# esp_heart.net
KiCad netlist of a schematic drawn in EAGLE
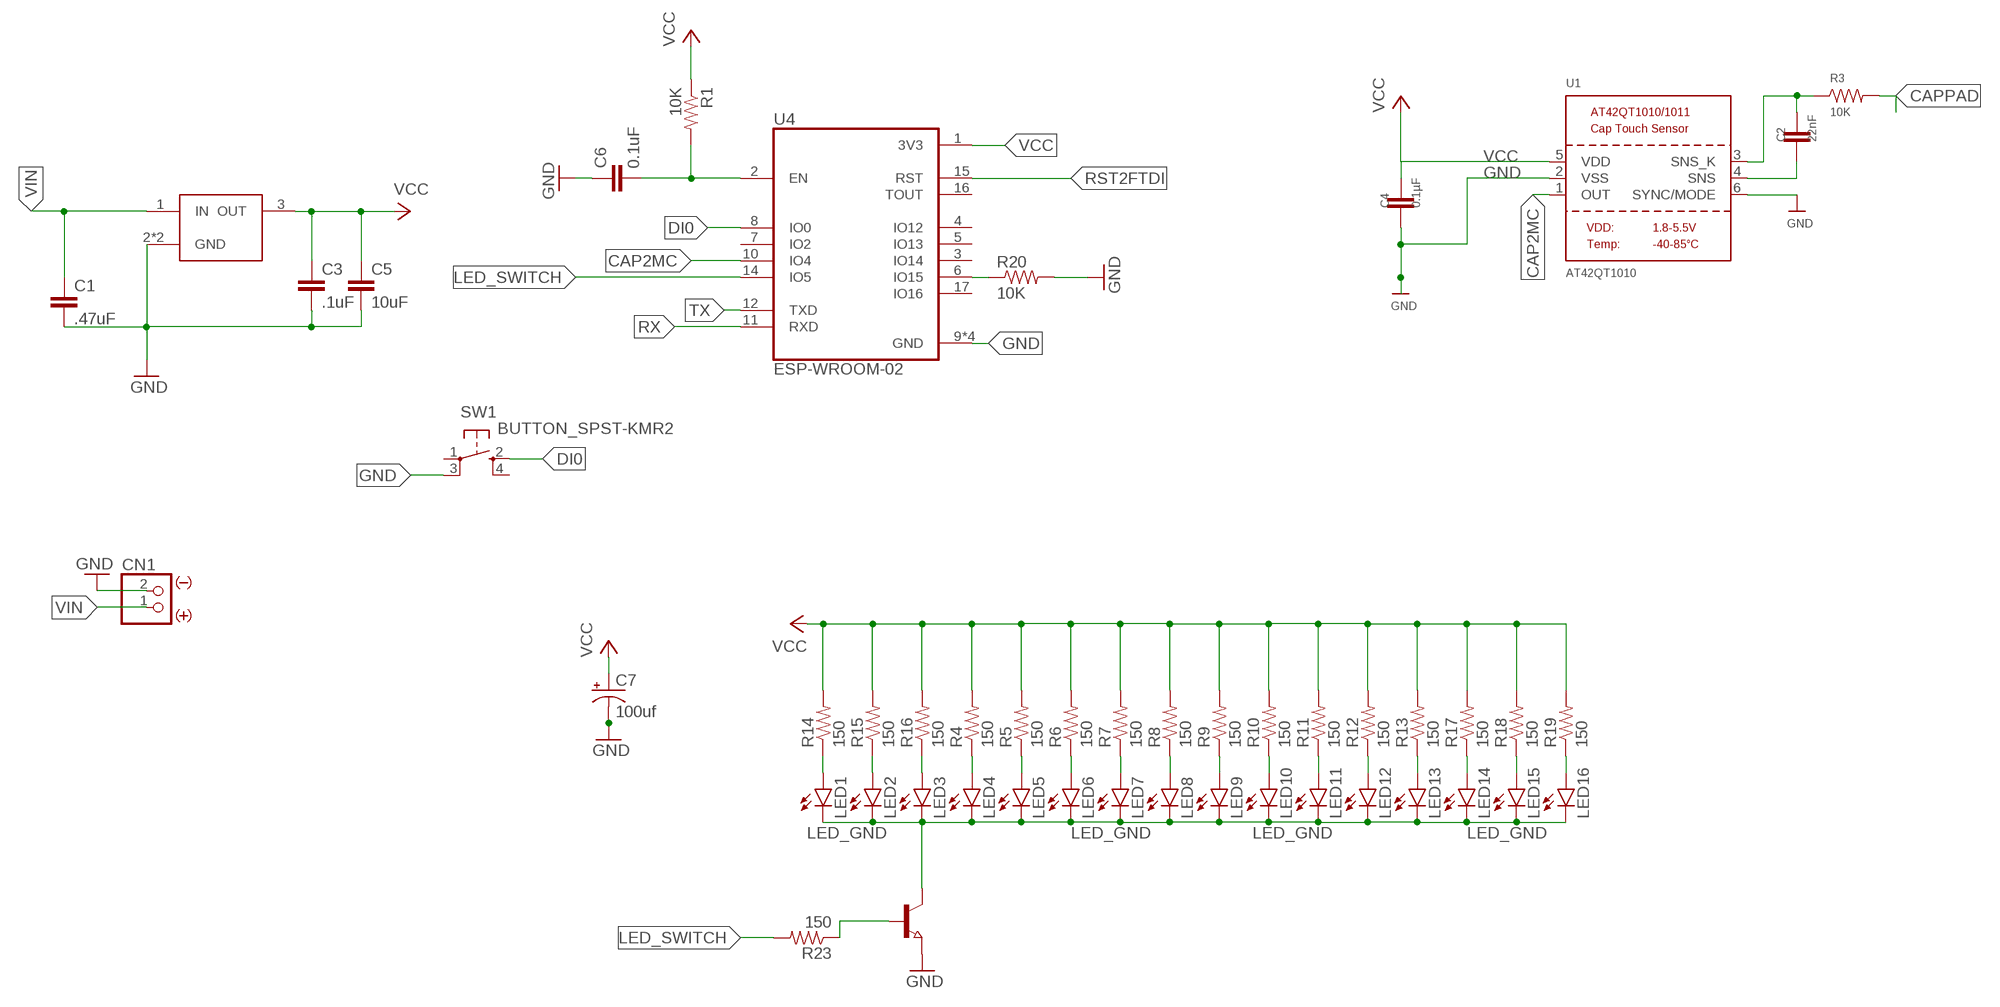
[diagram p0: schematic, sheet 1]

(export (version "E")
  (design (tool "Eeschema 10.0.6"))
  (components
    (comp (ref "C1")
      (value ".47uF")
      (footprint "eagle-import:0805")
      (libsource (lib "eagle-import") (part "CAP-0805"))
    )
    (comp (ref "C2")
      (value "22nF")
      (footprint "eagle-import:0805")
      (libsource (lib "eagle-import") (part "CAP-0805"))
    )
    (comp (ref "C3")
      (value ".1uF")
      (footprint "eagle-import:0805")
      (libsource (lib "eagle-import") (part "CAP-0805"))
    )
    (comp (ref "C4")
      (value "0.1µF")
      (footprint "eagle-import:0805")
      (libsource (lib "eagle-import") (part "CAP-0805"))
    )
    (comp (ref "C5")
      (value "10uF")
      (footprint "eagle-import:0805")
      (libsource (lib "eagle-import") (part "CAP-0805"))
    )
    (comp (ref "C6")
      (value "0.1uF")
      (footprint "eagle-import:0805")
      (libsource (lib "eagle-import") (part "CAP-0805"))
    )
    (comp (ref "C7")
      (value "100uf")
      (footprint "eagle-import:PANASONIC_D")
      (libsource (lib "eagle-import") (part "CAP_POLD"))
    )
    (comp (ref "CN1")
      (value "JST_2PIN_BATTERY-SMT-HORIZ")
      (footprint "eagle-import:JST-PH-2-SMT-RA")
      (libsource (lib "eagle-import") (part "JST_2PIN_BATTERY-SMT-HORIZ"))
    )
    (comp (ref "LED1")
      (value "LED0603")
      (footprint "eagle-import:LED-0603")
      (libsource (lib "eagle-import") (part "LED0603"))
    )
    (comp (ref "LED2")
      (value "LED0603")
      (footprint "eagle-import:LED-0603")
      (libsource (lib "eagle-import") (part "LED0603"))
    )
    (comp (ref "LED3")
      (value "LED0603")
      (footprint "eagle-import:LED-0603")
      (libsource (lib "eagle-import") (part "LED0603"))
    )
    (comp (ref "LED4")
      (value "LED0603")
      (footprint "eagle-import:LED-0603")
      (libsource (lib "eagle-import") (part "LED0603"))
    )
    (comp (ref "LED5")
      (value "LED0603")
      (footprint "eagle-import:LED-0603")
      (libsource (lib "eagle-import") (part "LED0603"))
    )
    (comp (ref "LED6")
      (value "LED0603")
      (footprint "eagle-import:LED-0603")
      (libsource (lib "eagle-import") (part "LED0603"))
    )
    (comp (ref "LED7")
      (value "LED0603")
      (footprint "eagle-import:LED-0603")
      (libsource (lib "eagle-import") (part "LED0603"))
    )
    (comp (ref "LED8")
      (value "LED0603")
      (footprint "eagle-import:LED-0603")
      (libsource (lib "eagle-import") (part "LED0603"))
    )
    (comp (ref "LED9")
      (value "LED0603")
      (footprint "eagle-import:LED-0603")
      (libsource (lib "eagle-import") (part "LED0603"))
    )
    (comp (ref "LED10")
      (value "LED0603")
      (footprint "eagle-import:LED-0603")
      (libsource (lib "eagle-import") (part "LED0603"))
    )
    (comp (ref "LED11")
      (value "LED0603")
      (footprint "eagle-import:LED-0603")
      (libsource (lib "eagle-import") (part "LED0603"))
    )
    (comp (ref "LED12")
      (value "LED0603")
      (footprint "eagle-import:LED-0603")
      (libsource (lib "eagle-import") (part "LED0603"))
    )
    (comp (ref "LED13")
      (value "LED0603")
      (footprint "eagle-import:LED-0603")
      (libsource (lib "eagle-import") (part "LED0603"))
    )
    (comp (ref "LED14")
      (value "LED0603")
      (footprint "eagle-import:LED-0603")
      (libsource (lib "eagle-import") (part "LED0603"))
    )
    (comp (ref "LED15")
      (value "LED0603")
      (footprint "eagle-import:LED-0603")
      (libsource (lib "eagle-import") (part "LED0603"))
    )
    (comp (ref "LED16")
      (value "LED0603")
      (footprint "eagle-import:LED-0603")
      (libsource (lib "eagle-import") (part "LED0603"))
    )
    (comp (ref "Q5")
      (value "TRANSISTOR-NPN-SOT23")
      (footprint "eagle-import:SOT23")
      (libsource (lib "eagle-import") (part "TRANSISTOR-NPN-SOT23"))
    )
    (comp (ref "R1")
      (value "10K")
      (footprint "eagle-import:0805")
      (libsource (lib "eagle-import") (part "RESISTOR-0805"))
    )
    (comp (ref "R3")
      (value "10K")
      (footprint "eagle-import:0805")
      (libsource (lib "eagle-import") (part "RESISTOR-0805"))
    )
    (comp (ref "R4")
      (value "150")
      (footprint "eagle-import:0603-RES")
      (libsource (lib "eagle-import") (part "RESISTOR0603"))
    )
    (comp (ref "R5")
      (value "150")
      (footprint "eagle-import:0603-RES")
      (libsource (lib "eagle-import") (part "RESISTOR0603"))
    )
    (comp (ref "R6")
      (value "150")
      (footprint "eagle-import:0603-RES")
      (libsource (lib "eagle-import") (part "RESISTOR0603"))
    )
    (comp (ref "R7")
      (value "150")
      (footprint "eagle-import:0603-RES")
      (libsource (lib "eagle-import") (part "RESISTOR0603"))
    )
    (comp (ref "R8")
      (value "150")
      (footprint "eagle-import:0603-RES")
      (libsource (lib "eagle-import") (part "RESISTOR0603"))
    )
    (comp (ref "R9")
      (value "150")
      (footprint "eagle-import:0603-RES")
      (libsource (lib "eagle-import") (part "RESISTOR0603"))
    )
    (comp (ref "R10")
      (value "150")
      (footprint "eagle-import:0603-RES")
      (libsource (lib "eagle-import") (part "RESISTOR0603"))
    )
    (comp (ref "R11")
      (value "150")
      (footprint "eagle-import:0603-RES")
      (libsource (lib "eagle-import") (part "RESISTOR0603"))
    )
    (comp (ref "R12")
      (value "150")
      (footprint "eagle-import:0603-RES")
      (libsource (lib "eagle-import") (part "RESISTOR0603"))
    )
    (comp (ref "R13")
      (value "150")
      (footprint "eagle-import:0603-RES")
      (libsource (lib "eagle-import") (part "RESISTOR0603"))
    )
    (comp (ref "R14")
      (value "150")
      (footprint "eagle-import:0603-RES")
      (libsource (lib "eagle-import") (part "RESISTOR0603"))
    )
    (comp (ref "R15")
      (value "150")
      (footprint "eagle-import:0603-RES")
      (libsource (lib "eagle-import") (part "RESISTOR0603"))
    )
    (comp (ref "R16")
      (value "150")
      (footprint "eagle-import:0603-RES")
      (libsource (lib "eagle-import") (part "RESISTOR0603"))
    )
    (comp (ref "R17")
      (value "150")
      (footprint "eagle-import:0603-RES")
      (libsource (lib "eagle-import") (part "RESISTOR0603"))
    )
    (comp (ref "R18")
      (value "150")
      (footprint "eagle-import:0603-RES")
      (libsource (lib "eagle-import") (part "RESISTOR0603"))
    )
    (comp (ref "R19")
      (value "150")
      (footprint "eagle-import:0603-RES")
      (libsource (lib "eagle-import") (part "RESISTOR0603"))
    )
    (comp (ref "R20")
      (value "10K")
      (footprint "eagle-import:0805")
      (libsource (lib "eagle-import") (part "RESISTOR-0805"))
    )
    (comp (ref "R23")
      (value "150")
      (footprint "eagle-import:0805")
      (libsource (lib "eagle-import") (part "RESISTOR-0805"))
    )
    (comp (ref "SW1")
      (value "BUTTON_SPST-KMR2")
      (footprint "eagle-import:KMR2")
      (libsource (lib "eagle-import") (part "BUTTON_SPST-KMR2"))
    )
    (comp (ref "U$1")
      (value "REGULATOR3.3V-0.5A-UA78M33CDCYR")
      (footprint "eagle-import:SOT223")
      (libsource (lib "eagle-import") (part "REGULATOR3.3V-0.5A-UA78M33CDCYR"))
    )
    (comp (ref "U1")
      (value "AT42QT1010")
      (footprint "eagle-import:SOT23-6")
      (libsource (lib "eagle-import") (part "AT42QT1010/1"))
    )
    (comp (ref "U4")
      (value "ESP-WROOM-02")
      (footprint "eagle-import:MODULE_ESP-WROOM-02")
      (fields (field (name "MF") "Espressif Systems"))
      (libsource (lib "eagle-import") (part "ESP-WROOM-02"))
    )
  )
  (nets
    (net (code "1") (name "/LED_GND") (class "Default")
      (node (ref "LED1") (pin "C") (pinfunction "C_C") (pintype "passive"))
      (node (ref "LED10") (pin "C") (pinfunction "C_C") (pintype "passive"))
      (node (ref "LED11") (pin "C") (pinfunction "C_C") (pintype "passive"))
      (node (ref "LED12") (pin "C") (pinfunction "C_C") (pintype "passive"))
      (node (ref "LED13") (pin "C") (pinfunction "C_C") (pintype "passive"))
      (node (ref "LED14") (pin "C") (pinfunction "C_C") (pintype "passive"))
      (node (ref "LED15") (pin "C") (pinfunction "C_C") (pintype "passive"))
      (node (ref "LED16") (pin "C") (pinfunction "C_C") (pintype "passive"))
      (node (ref "LED2") (pin "C") (pinfunction "C_C") (pintype "passive"))
      (node (ref "LED3") (pin "C") (pinfunction "C_C") (pintype "passive"))
      (node (ref "LED4") (pin "C") (pinfunction "C_C") (pintype "passive"))
      (node (ref "LED5") (pin "C") (pinfunction "C_C") (pintype "passive"))
      (node (ref "LED6") (pin "C") (pinfunction "C_C") (pintype "passive"))
      (node (ref "LED7") (pin "C") (pinfunction "C_C") (pintype "passive"))
      (node (ref "LED8") (pin "C") (pinfunction "C_C") (pintype "passive"))
      (node (ref "LED9") (pin "C") (pinfunction "C_C") (pintype "passive"))
      (node (ref "Q5") (pin "3") (pinfunction "C_3") (pintype "passive"))
    )
    (net (code "2") (name "CAP2MC") (class "Default")
      (node (ref "U1") (pin "1") (pinfunction "OUT_1") (pintype "output"))
      (node (ref "U4") (pin "10") (pinfunction "IO4_10") (pintype "bidirectional"))
    )
    (net (code "3") (name "CAPPAD") (class "Default")
      (node (ref "R3") (pin "2") (pinfunction "2_2") (pintype "passive"))
    )
    (net (code "4") (name "DI0") (class "Default")
      (node (ref "SW1") (pin "2") (pinfunction "S_2") (pintype "passive"))
      (node (ref "U4") (pin "8") (pinfunction "IO0_8") (pintype "bidirectional"))
    )
    (net (code "5") (name "GND") (class "Default")
      (node (ref "C1") (pin "2") (pinfunction "2_2") (pintype "passive"))
      (node (ref "C3") (pin "2") (pinfunction "2_2") (pintype "passive"))
      (node (ref "C4") (pin "2") (pinfunction "2_2") (pintype "passive"))
      (node (ref "C5") (pin "2") (pinfunction "2_2") (pintype "passive"))
      (node (ref "C6") (pin "1") (pinfunction "1_1") (pintype "passive"))
      (node (ref "C7") (pin "-") (pinfunction "-_-") (pintype "passive"))
      (node (ref "CN1") (pin "2") (pinfunction "1_2") (pintype "passive"))
      (node (ref "Q5") (pin "2") (pinfunction "E_2") (pintype "passive"))
      (node (ref "R20") (pin "2") (pinfunction "2_2") (pintype "passive"))
      (node (ref "SW1") (pin "3") (pinfunction "P1_3") (pintype "passive"))
      (node (ref "U$1") (pin "2") (pinfunction "GND_2") (pintype "bidirectional"))
      (node (ref "U$1") (pin "4") (pinfunction "GND_4") (pintype "bidirectional"))
      (node (ref "U1") (pin "2") (pinfunction "VSS_2") (pintype "power_in"))
      (node (ref "U1") (pin "6") (pinfunction "SYNC/MODE_6") (pintype "input"))
      (node (ref "U4") (pin "13") (pinfunction "GND_13") (pintype "power_in"))
      (node (ref "U4") (pin "18") (pinfunction "GND_18") (pintype "power_in"))
      (node (ref "U4") (pin "19") (pinfunction "GND_19") (pintype "power_in"))
      (node (ref "U4") (pin "9") (pinfunction "GND_9") (pintype "power_in"))
    )
    (net (code "6") (name "LED_SWITCH") (class "Default")
      (node (ref "R23") (pin "2") (pinfunction "2_2") (pintype "passive"))
      (node (ref "U4") (pin "14") (pinfunction "IO5_14") (pintype "open_collector"))
    )
    (net (code "7") (name "Net-(LED1-PadA)") (class "Default")
      (node (ref "LED1") (pin "A") (pinfunction "A_A") (pintype "passive"))
      (node (ref "R14") (pin "1") (pinfunction "1_1") (pintype "passive"))
    )
    (net (code "8") (name "Net-(LED2-PadA)") (class "Default")
      (node (ref "LED2") (pin "A") (pinfunction "A_A") (pintype "passive"))
      (node (ref "R15") (pin "1") (pinfunction "1_1") (pintype "passive"))
    )
    (net (code "9") (name "Net-(LED3-PadA)") (class "Default")
      (node (ref "LED3") (pin "A") (pinfunction "A_A") (pintype "passive"))
      (node (ref "R16") (pin "1") (pinfunction "1_1") (pintype "passive"))
    )
    (net (code "10") (name "Net-(LED4-PadA)") (class "Default")
      (node (ref "LED4") (pin "A") (pinfunction "A_A") (pintype "passive"))
      (node (ref "R4") (pin "1") (pinfunction "1_1") (pintype "passive"))
    )
    (net (code "11") (name "Net-(LED5-PadA)") (class "Default")
      (node (ref "LED5") (pin "A") (pinfunction "A_A") (pintype "passive"))
      (node (ref "R5") (pin "1") (pinfunction "1_1") (pintype "passive"))
    )
    (net (code "12") (name "Net-(LED6-PadA)") (class "Default")
      (node (ref "LED6") (pin "A") (pinfunction "A_A") (pintype "passive"))
      (node (ref "R6") (pin "1") (pinfunction "1_1") (pintype "passive"))
    )
    (net (code "13") (name "Net-(LED7-PadA)") (class "Default")
      (node (ref "LED7") (pin "A") (pinfunction "A_A") (pintype "passive"))
      (node (ref "R7") (pin "1") (pinfunction "1_1") (pintype "passive"))
    )
    (net (code "14") (name "Net-(LED8-PadA)") (class "Default")
      (node (ref "LED8") (pin "A") (pinfunction "A_A") (pintype "passive"))
      (node (ref "R8") (pin "1") (pinfunction "1_1") (pintype "passive"))
    )
    (net (code "15") (name "Net-(LED9-PadA)") (class "Default")
      (node (ref "LED9") (pin "A") (pinfunction "A_A") (pintype "passive"))
      (node (ref "R9") (pin "1") (pinfunction "1_1") (pintype "passive"))
    )
    (net (code "16") (name "Net-(LED10-PadA)") (class "Default")
      (node (ref "LED10") (pin "A") (pinfunction "A_A") (pintype "passive"))
      (node (ref "R10") (pin "1") (pinfunction "1_1") (pintype "passive"))
    )
    (net (code "17") (name "Net-(LED11-PadA)") (class "Default")
      (node (ref "LED11") (pin "A") (pinfunction "A_A") (pintype "passive"))
      (node (ref "R11") (pin "1") (pinfunction "1_1") (pintype "passive"))
    )
    (net (code "18") (name "Net-(LED12-PadA)") (class "Default")
      (node (ref "LED12") (pin "A") (pinfunction "A_A") (pintype "passive"))
      (node (ref "R12") (pin "1") (pinfunction "1_1") (pintype "passive"))
    )
    (net (code "19") (name "Net-(LED13-PadA)") (class "Default")
      (node (ref "LED13") (pin "A") (pinfunction "A_A") (pintype "passive"))
      (node (ref "R13") (pin "1") (pinfunction "1_1") (pintype "passive"))
    )
    (net (code "20") (name "Net-(LED14-PadA)") (class "Default")
      (node (ref "LED14") (pin "A") (pinfunction "A_A") (pintype "passive"))
      (node (ref "R17") (pin "1") (pinfunction "1_1") (pintype "passive"))
    )
    (net (code "21") (name "Net-(LED15-PadA)") (class "Default")
      (node (ref "LED15") (pin "A") (pinfunction "A_A") (pintype "passive"))
      (node (ref "R18") (pin "1") (pinfunction "1_1") (pintype "passive"))
    )
    (net (code "22") (name "Net-(LED16-PadA)") (class "Default")
      (node (ref "LED16") (pin "A") (pinfunction "A_A") (pintype "passive"))
      (node (ref "R19") (pin "1") (pinfunction "1_1") (pintype "passive"))
    )
    (net (code "23") (name "Net-(Q5-B)") (class "Default")
      (node (ref "Q5") (pin "1") (pinfunction "B_1") (pintype "passive"))
      (node (ref "R23") (pin "1") (pinfunction "1_1") (pintype "passive"))
    )
    (net (code "24") (name "Net-(U1-SNS)") (class "Default")
      (node (ref "C2") (pin "2") (pinfunction "2_2") (pintype "passive"))
      (node (ref "U1") (pin "4") (pinfunction "SNS_4") (pintype "bidirectional"))
    )
    (net (code "25") (name "Net-(U1-SNS_K)") (class "Default")
      (node (ref "C2") (pin "1") (pinfunction "1_1") (pintype "passive"))
      (node (ref "R3") (pin "1") (pinfunction "1_1") (pintype "passive"))
      (node (ref "U1") (pin "3") (pinfunction "SNS_K_3") (pintype "bidirectional"))
    )
    (net (code "26") (name "Net-(U4-EN)") (class "Default")
      (node (ref "C6") (pin "2") (pinfunction "2_2") (pintype "passive"))
      (node (ref "R1") (pin "2") (pinfunction "2_2") (pintype "passive"))
      (node (ref "U4") (pin "2") (pinfunction "EN_2") (pintype "input"))
    )
    (net (code "27") (name "Net-(U4-IO15)") (class "Default")
      (node (ref "R20") (pin "1") (pinfunction "1_1") (pintype "passive"))
      (node (ref "U4") (pin "6") (pinfunction "IO15_6") (pintype "bidirectional"))
    )
    (net (code "28") (name "RST2FTDI") (class "Default")
      (node (ref "U4") (pin "15") (pinfunction "RST_15") (pintype "bidirectional"))
    )
    (net (code "29") (name "RX") (class "Default")
      (node (ref "U4") (pin "11") (pinfunction "RXD_11") (pintype "bidirectional"))
    )
    (net (code "30") (name "TX") (class "Default")
      (node (ref "U4") (pin "12") (pinfunction "TXD_12") (pintype "bidirectional"))
    )
    (net (code "31") (name "VCC") (class "Default")
      (node (ref "C3") (pin "1") (pinfunction "1_1") (pintype "passive"))
      (node (ref "C4") (pin "1") (pinfunction "1_1") (pintype "passive"))
      (node (ref "C5") (pin "1") (pinfunction "1_1") (pintype "passive"))
      (node (ref "C7") (pin "+") (pinfunction "+_+") (pintype "passive"))
      (node (ref "R1") (pin "1") (pinfunction "1_1") (pintype "passive"))
      (node (ref "R10") (pin "2") (pinfunction "2_2") (pintype "passive"))
      (node (ref "R11") (pin "2") (pinfunction "2_2") (pintype "passive"))
      (node (ref "R12") (pin "2") (pinfunction "2_2") (pintype "passive"))
      (node (ref "R13") (pin "2") (pinfunction "2_2") (pintype "passive"))
      (node (ref "R14") (pin "2") (pinfunction "2_2") (pintype "passive"))
      (node (ref "R15") (pin "2") (pinfunction "2_2") (pintype "passive"))
      (node (ref "R16") (pin "2") (pinfunction "2_2") (pintype "passive"))
      (node (ref "R17") (pin "2") (pinfunction "2_2") (pintype "passive"))
      (node (ref "R18") (pin "2") (pinfunction "2_2") (pintype "passive"))
      (node (ref "R19") (pin "2") (pinfunction "2_2") (pintype "passive"))
      (node (ref "R4") (pin "2") (pinfunction "2_2") (pintype "passive"))
      (node (ref "R5") (pin "2") (pinfunction "2_2") (pintype "passive"))
      (node (ref "R6") (pin "2") (pinfunction "2_2") (pintype "passive"))
      (node (ref "R7") (pin "2") (pinfunction "2_2") (pintype "passive"))
      (node (ref "R8") (pin "2") (pinfunction "2_2") (pintype "passive"))
      (node (ref "R9") (pin "2") (pinfunction "2_2") (pintype "passive"))
      (node (ref "U$1") (pin "3") (pinfunction "OUT_3") (pintype "bidirectional"))
      (node (ref "U1") (pin "5") (pinfunction "VDD_5") (pintype "power_in"))
      (node (ref "U4") (pin "1") (pinfunction "3V3_1") (pintype "power_in"))
    )
    (net (code "32") (name "VIN") (class "Default")
      (node (ref "C1") (pin "1") (pinfunction "1_1") (pintype "passive"))
      (node (ref "CN1") (pin "1") (pinfunction "2_1") (pintype "passive"))
      (node (ref "U$1") (pin "1") (pinfunction "IN_1") (pintype "bidirectional"))
    )
    (net (code "33") (name "unconnected-(SW1-P-Pad1)") (class "Default")
      (node (ref "SW1") (pin "1") (pinfunction "P_1") (pintype "passive"))
    )
    (net (code "34") (name "unconnected-(SW1-S1-Pad4)") (class "Default")
      (node (ref "SW1") (pin "4") (pinfunction "S1_4") (pintype "passive"))
    )
    (net (code "35") (name "unconnected-(U4-IO2-Pad7)") (class "Default")
      (node (ref "U4") (pin "7") (pinfunction "IO2_7") (pintype "bidirectional"))
    )
    (net (code "36") (name "unconnected-(U4-IO12-Pad4)") (class "Default")
      (node (ref "U4") (pin "4") (pinfunction "IO12_4") (pintype "bidirectional"))
    )
    (net (code "37") (name "unconnected-(U4-IO13-Pad5)") (class "Default")
      (node (ref "U4") (pin "5") (pinfunction "IO13_5") (pintype "bidirectional"))
    )
    (net (code "38") (name "unconnected-(U4-IO14-Pad3)") (class "Default")
      (node (ref "U4") (pin "3") (pinfunction "IO14_3") (pintype "bidirectional"))
    )
    (net (code "39") (name "unconnected-(U4-IO16-Pad17)") (class "Default")
      (node (ref "U4") (pin "17") (pinfunction "IO16_17") (pintype "bidirectional"))
    )
    (net (code "40") (name "unconnected-(U4-TOUT-Pad16)") (class "Default")
      (node (ref "U4") (pin "16") (pinfunction "TOUT_16") (pintype "bidirectional"))
    )
  )
)
